# MicroPLSheet.net
KiCad netlist of a schematic drawn in Altium Designer
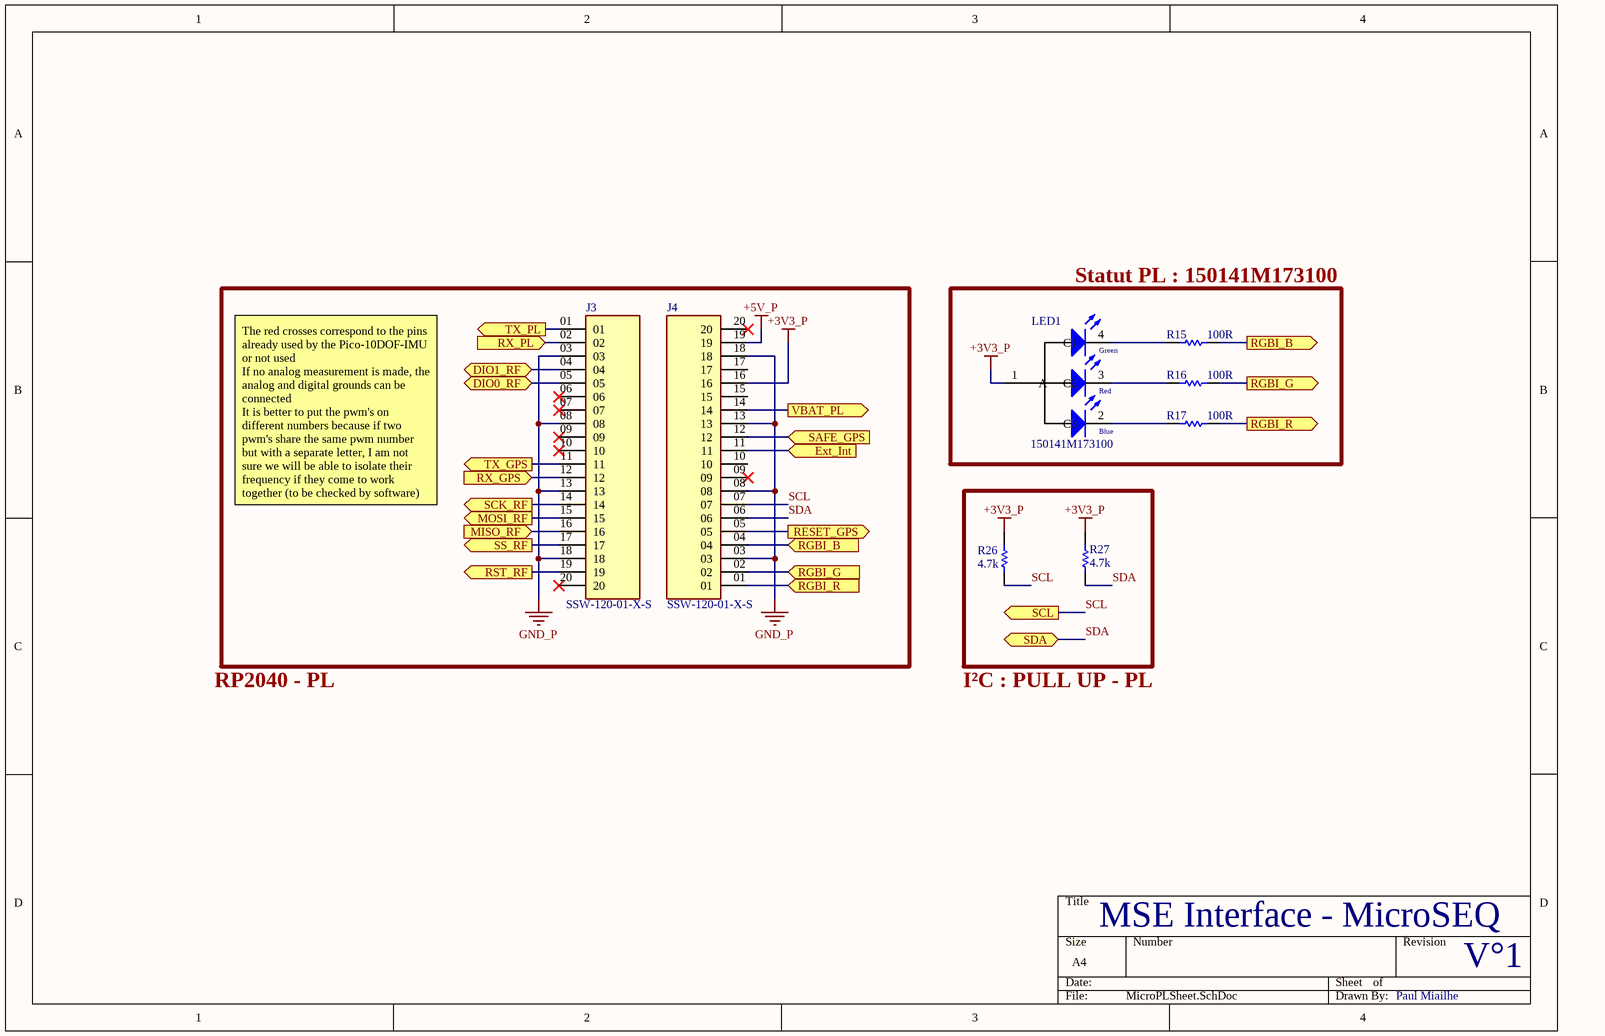
[diagram p0: MicroPLSheet.SchDoc]

(export (version "E")
  (design (tool "Eeschema 10.0.6"))
  (components
    (comp (ref "J3")
      (value "SSW-120-01-X-S")
      (footprint "SAMTEC_SSW-120-01-X-S")
      (description "SSW - Samtec 2.54mm Single Row Straight Socket Strip 8.5 Profile - Fast Stock")
      (fields (field (name "MP") "SSW-120-01-G-S") (field (name "MF") "Samtec"))
      (libsource (lib "Saint-Étienne School of Mines- Mines Space") (part "SSW-120-01-X-S"))
    )
    (comp (ref "J4")
      (value "SSW-120-01-X-S")
      (footprint "SAMTEC_SSW-120-01-X-S")
      (description "SSW - Samtec 2.54mm Single Row Straight Socket Strip 8.5 Profile - Fast Stock")
      (fields (field (name "MP") "SSW-120-01-G-S") (field (name "MF") "Samtec"))
      (libsource (lib "") (part "SSW-120-01-X-S_1"))
    )
    (comp (ref "LED1")
      (value "150141M173100")
      (footprint "3528_A")
      (description "SMD Full-Color Top LED, WL-SFTW, Red & Green & Blue")
      (fields (field (name "MANUFACTURER") "Wuerth Elektronik"))
      (libsource (lib "Altium Content Vault") (part "WE-LED_RGB_A1B2R3G4-4"))
    )
    (comp (ref "R15")
      (value "ERJ-3EKF1000V")
      (footprint "RESC1608X55X30LL15T15")
      (fields
        (field (name "MANUFACTURER") "Panasonic")
        (field (name "MANUFACTURER PART NUMBER") "ERJ3EKF1000V")
        (field (name "RESISTANCE") "100R")
        (field (name "TOLERANCE") "1%")
      )
      (libsource (lib "Altium Content Vault") (part "RES"))
    )
    (comp (ref "R16")
      (value "ERJ-3EKF1000V")
      (footprint "RESC1608X55X30LL15T15")
      (fields
        (field (name "MANUFACTURER") "Panasonic")
        (field (name "MANUFACTURER PART NUMBER") "ERJ3EKF1000V")
        (field (name "RESISTANCE") "100R")
        (field (name "TOLERANCE") "1%")
      )
      (libsource (lib "Altium Content Vault") (part "RES"))
    )
    (comp (ref "R17")
      (value "ERJ-3EKF1000V")
      (footprint "RESC1608X55X30LL15T15")
      (fields
        (field (name "MANUFACTURER") "Panasonic")
        (field (name "MANUFACTURER PART NUMBER") "ERJ3EKF1000V")
        (field (name "RESISTANCE") "100R")
        (field (name "TOLERANCE") "1%")
      )
      (libsource (lib "Altium Content Vault") (part "RES"))
    )
    (comp (ref "R26")
      (value "RC0603FR-074K7L")
      (footprint "RESC1608X55X25LL10T15")
      (description "Chip Resistor, 4.7 KOhm, +/- 1%, 0.1 W, -55 to 155 degC, 0603 (1608 Metric), RoHS, Tape and Reel")
      (fields
        (field (name "MANUFACTURER") "Yageo")
        (field (name "RESISTANCE") "4.7k")
        (field (name "TOLERANCE") "1%")
      )
      (libsource (lib "Altium Content Vault") (part "RES-2"))
    )
    (comp (ref "R27")
      (value "RC0603FR-074K7L")
      (footprint "RESC1608X55X25LL10T15")
      (description "Chip Resistor, 4.7 KOhm, +/- 1%, 0.1 W, -55 to 155 degC, 0603 (1608 Metric), RoHS, Tape and Reel")
      (fields
        (field (name "MANUFACTURER") "Yageo")
        (field (name "RESISTANCE") "4.7k")
        (field (name "TOLERANCE") "1%")
      )
      (libsource (lib "Altium Content Vault") (part "RES-2"))
    )
  )
  (nets
    (net (code "1") (name "+3V3_P") (class "Default")
      (node (ref "J4") (pin "16") (pinfunction "16_16") (pintype "passive"))
      (node (ref "LED1") (pin "1") (pinfunction "A_1") (pintype "passive"))
      (node (ref "R26") (pin "2") (pinfunction "2_2") (pintype "passive"))
      (node (ref "R27") (pin "2") (pinfunction "2_2") (pintype "passive"))
    )
    (net (code "2") (name "+5V_P") (class "Default")
      (node (ref "J4") (pin "19") (pinfunction "19_19") (pintype "passive"))
    )
    (net (code "3") (name "/DIO0_RF") (class "Default")
      (node (ref "J3") (pin "05") (pinfunction "05_05") (pintype "passive"))
    )
    (net (code "4") (name "/DIO1_RF") (class "Default")
      (node (ref "J3") (pin "04") (pinfunction "04_04") (pintype "passive"))
    )
    (net (code "5") (name "/Ext_Int") (class "Default")
      (node (ref "J4") (pin "11") (pinfunction "11_11") (pintype "passive"))
    )
    (net (code "6") (name "/MISO_RF") (class "Default")
      (node (ref "J3") (pin "16") (pinfunction "16_16") (pintype "passive"))
    )
    (net (code "7") (name "/MOSI_RF") (class "Default")
      (node (ref "J3") (pin "15") (pinfunction "15_15") (pintype "passive"))
    )
    (net (code "8") (name "/RESET_GPS") (class "Default")
      (node (ref "J4") (pin "05") (pinfunction "05_05") (pintype "passive"))
    )
    (net (code "9") (name "/RGBI_B") (class "Default")
      (node (ref "J4") (pin "04") (pinfunction "04_04") (pintype "passive"))
      (node (ref "R15") (pin "1") (pinfunction "1_1") (pintype "passive"))
    )
    (net (code "10") (name "/RGBI_G") (class "Default")
      (node (ref "J4") (pin "02") (pinfunction "02_02") (pintype "passive"))
      (node (ref "R16") (pin "1") (pinfunction "1_1") (pintype "passive"))
    )
    (net (code "11") (name "/RGBI_R") (class "Default")
      (node (ref "J4") (pin "01") (pinfunction "01_01") (pintype "passive"))
      (node (ref "R17") (pin "1") (pinfunction "1_1") (pintype "passive"))
    )
    (net (code "12") (name "/RST_RF") (class "Default")
      (node (ref "J3") (pin "19") (pinfunction "19_19") (pintype "passive"))
    )
    (net (code "13") (name "/RX_GPS") (class "Default")
      (node (ref "J3") (pin "12") (pinfunction "12_12") (pintype "passive"))
    )
    (net (code "14") (name "/RX_PL") (class "Default")
      (node (ref "J3") (pin "02") (pinfunction "02_02") (pintype "passive"))
    )
    (net (code "15") (name "/SAFE_GPS") (class "Default")
      (node (ref "J4") (pin "12") (pinfunction "12_12") (pintype "passive"))
    )
    (net (code "16") (name "/SCK_RF") (class "Default")
      (node (ref "J3") (pin "14") (pinfunction "14_14") (pintype "passive"))
    )
    (net (code "17") (name "/SCL") (class "Default")
      (node (ref "J4") (pin "07") (pinfunction "07_07") (pintype "passive"))
      (node (ref "R26") (pin "1") (pinfunction "1_1") (pintype "passive"))
    )
    (net (code "18") (name "/SDA") (class "Default")
      (node (ref "J4") (pin "06") (pinfunction "06_06") (pintype "passive"))
      (node (ref "R27") (pin "1") (pinfunction "1_1") (pintype "passive"))
    )
    (net (code "19") (name "/SS_RF") (class "Default")
      (node (ref "J3") (pin "17") (pinfunction "17_17") (pintype "passive"))
    )
    (net (code "20") (name "/TX_GPS") (class "Default")
      (node (ref "J3") (pin "11") (pinfunction "11_11") (pintype "passive"))
    )
    (net (code "21") (name "/TX_PL") (class "Default")
      (node (ref "J3") (pin "01") (pinfunction "01_01") (pintype "passive"))
    )
    (net (code "22") (name "/VBAT_PL") (class "Default")
      (node (ref "J4") (pin "14") (pinfunction "14_14") (pintype "passive"))
    )
    (net (code "23") (name "GND_P") (class "Default")
      (node (ref "J3") (pin "03") (pinfunction "03_03") (pintype "passive"))
      (node (ref "J3") (pin "08") (pinfunction "08_08") (pintype "passive"))
      (node (ref "J3") (pin "13") (pinfunction "13_13") (pintype "passive"))
      (node (ref "J3") (pin "18") (pinfunction "18_18") (pintype "passive"))
      (node (ref "J4") (pin "03") (pinfunction "03_03") (pintype "passive"))
      (node (ref "J4") (pin "08") (pinfunction "08_08") (pintype "passive"))
      (node (ref "J4") (pin "13") (pinfunction "13_13") (pintype "passive"))
      (node (ref "J4") (pin "18") (pinfunction "18_18") (pintype "passive"))
    )
    (net (code "24") (name "Net-(LED1-C1)") (class "Default")
      (node (ref "LED1") (pin "4") (pinfunction "C1_4") (pintype "passive"))
      (node (ref "R15") (pin "2") (pinfunction "2_2") (pintype "passive"))
    )
    (net (code "25") (name "Net-(LED1-C2)") (class "Default")
      (node (ref "LED1") (pin "3") (pinfunction "C2_3") (pintype "passive"))
      (node (ref "R16") (pin "2") (pinfunction "2_2") (pintype "passive"))
    )
    (net (code "26") (name "Net-(LED1-C3)") (class "Default")
      (node (ref "LED1") (pin "2") (pinfunction "C3_2") (pintype "passive"))
      (node (ref "R17") (pin "2") (pinfunction "2_2") (pintype "passive"))
    )
    (net (code "27") (name "unconnected-(J3-Pad06)") (class "Default")
      (node (ref "J3") (pin "06") (pinfunction "06_06") (pintype "passive+no_connect"))
    )
    (net (code "28") (name "unconnected-(J3-Pad07)") (class "Default")
      (node (ref "J3") (pin "07") (pinfunction "07_07") (pintype "passive+no_connect"))
    )
    (net (code "29") (name "unconnected-(J3-Pad09)") (class "Default")
      (node (ref "J3") (pin "09") (pinfunction "09_09") (pintype "passive+no_connect"))
    )
    (net (code "30") (name "unconnected-(J3-Pad10)") (class "Default")
      (node (ref "J3") (pin "10") (pinfunction "10_10") (pintype "passive+no_connect"))
    )
    (net (code "31") (name "unconnected-(J3-Pad20)") (class "Default")
      (node (ref "J3") (pin "20") (pinfunction "20_20") (pintype "passive+no_connect"))
    )
    (net (code "32") (name "unconnected-(J4-Pad09)") (class "Default")
      (node (ref "J4") (pin "09") (pinfunction "09_09") (pintype "passive+no_connect"))
    )
    (net (code "33") (name "unconnected-(J4-Pad10)") (class "Default")
      (node (ref "J4") (pin "10") (pinfunction "10_10") (pintype "passive"))
    )
    (net (code "34") (name "unconnected-(J4-Pad15)") (class "Default")
      (node (ref "J4") (pin "15") (pinfunction "15_15") (pintype "passive"))
    )
    (net (code "35") (name "unconnected-(J4-Pad17)") (class "Default")
      (node (ref "J4") (pin "17") (pinfunction "17_17") (pintype "passive"))
    )
    (net (code "36") (name "unconnected-(J4-Pad20)") (class "Default")
      (node (ref "J4") (pin "20") (pinfunction "20_20") (pintype "passive+no_connect"))
    )
  )
)
